# MB_Conn.net
KiCad netlist of a schematic drawn in Altium Designer
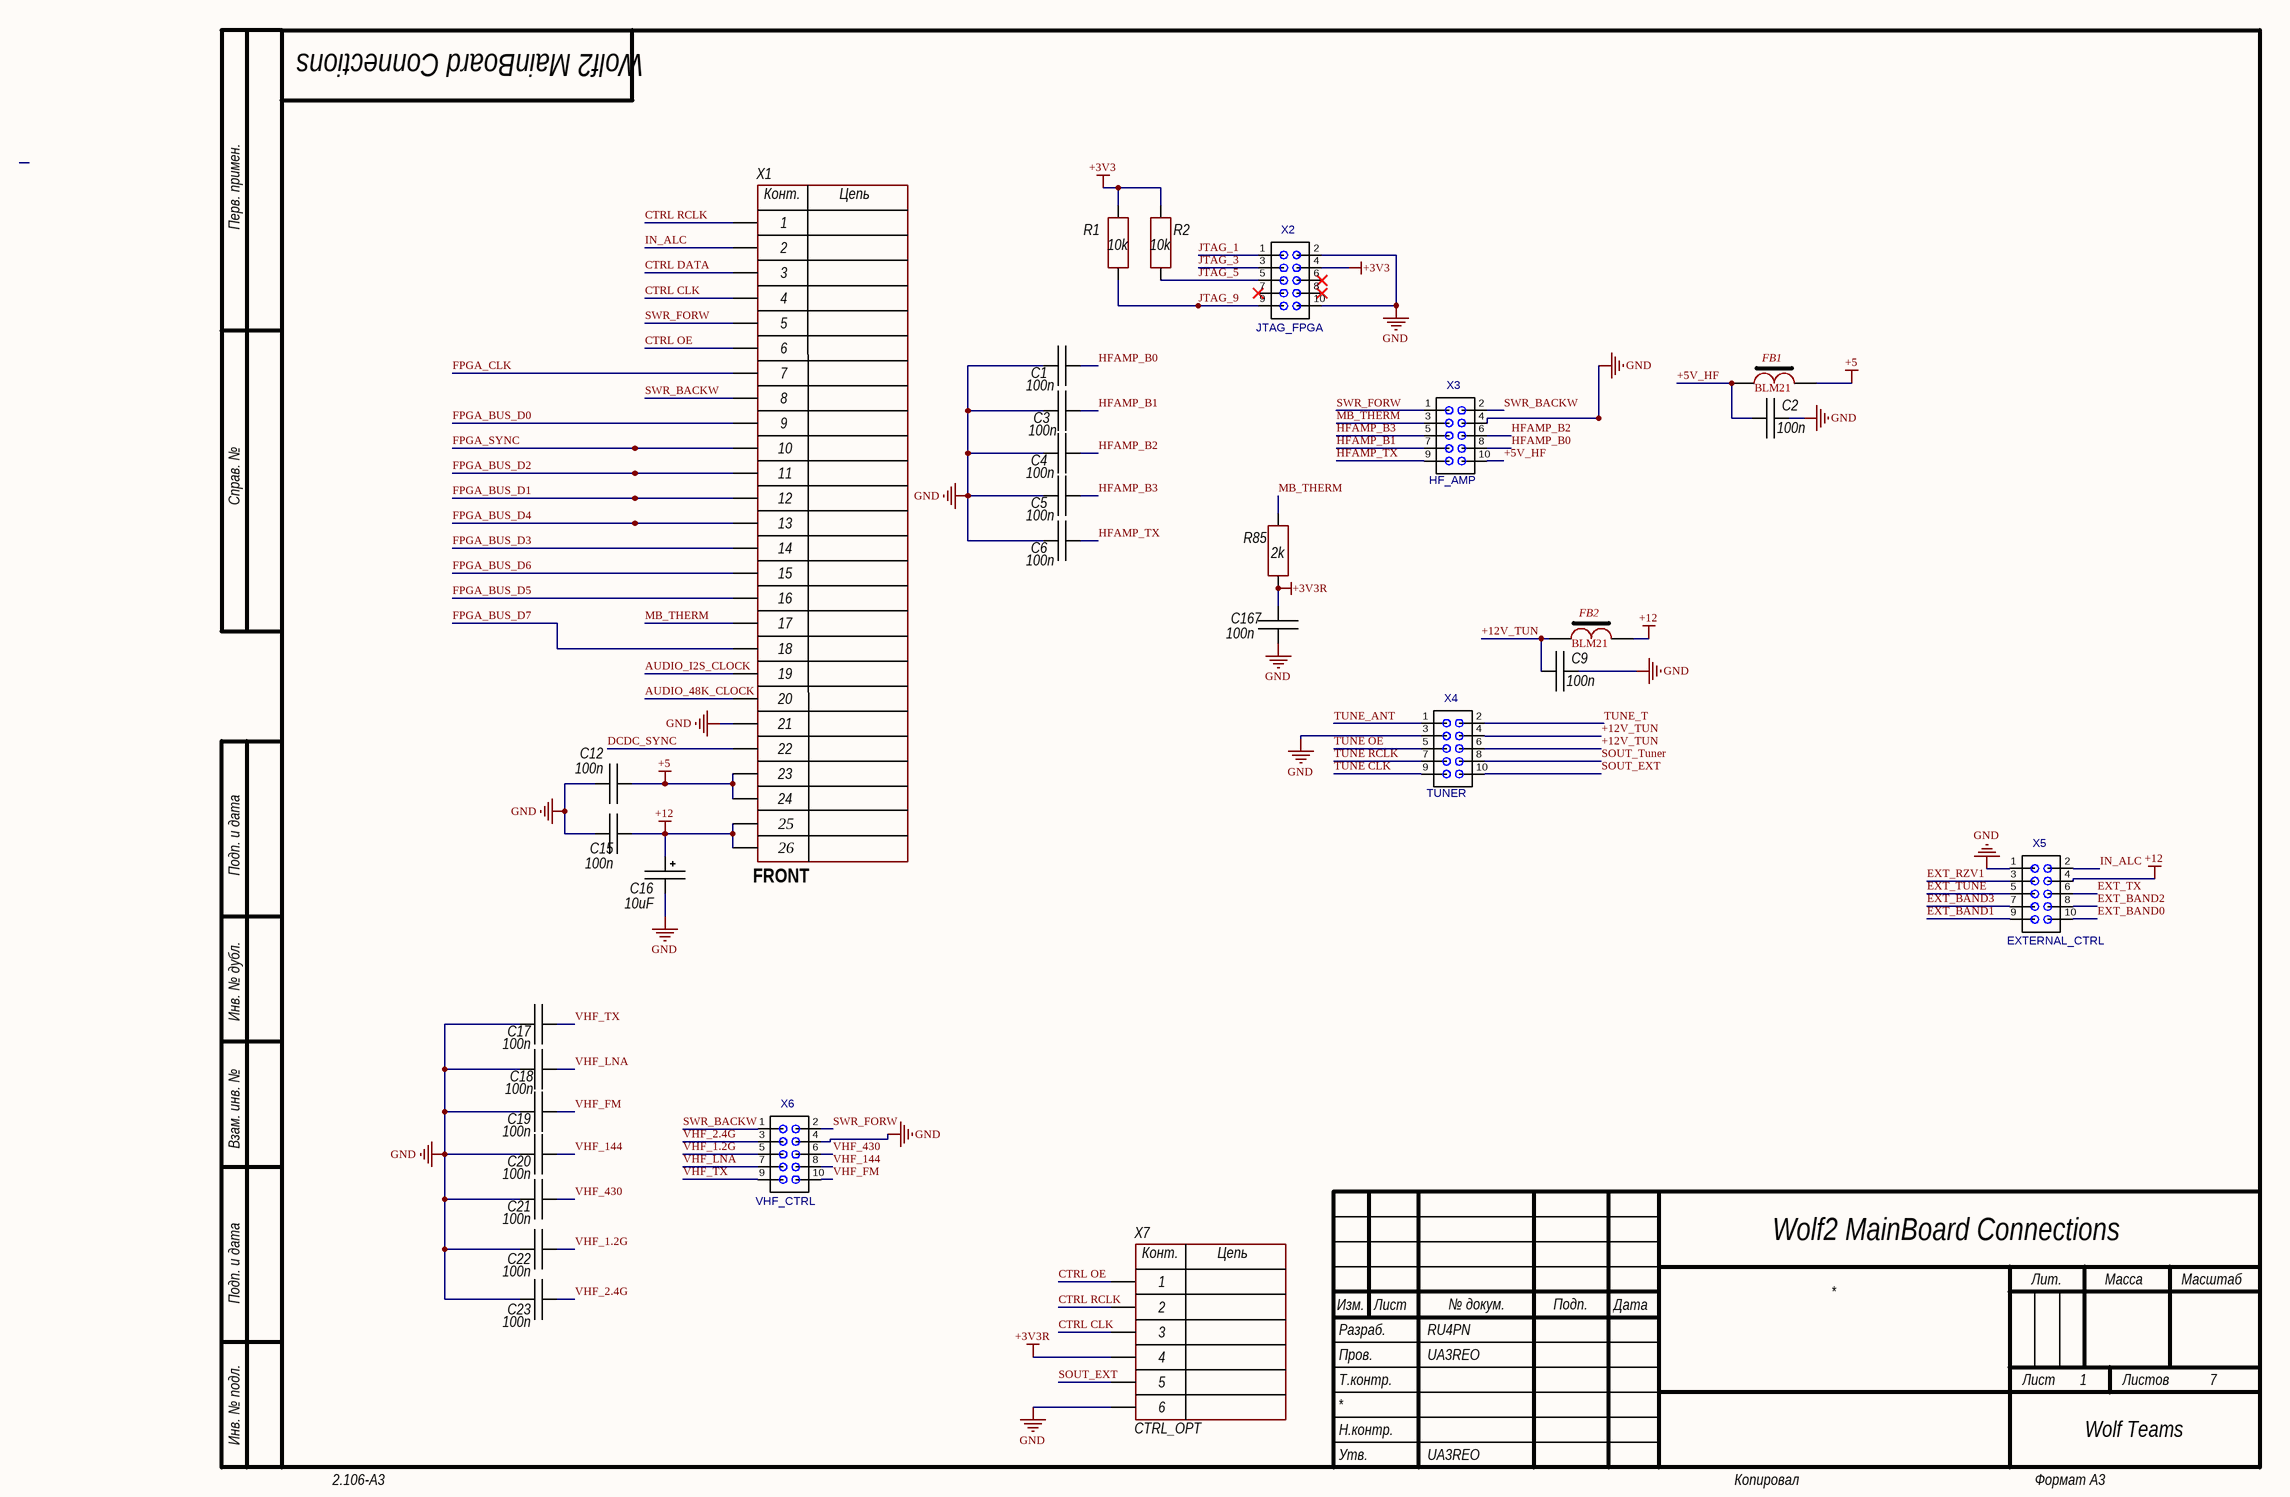
[diagram p0: MB_Conn.SchDoc]

(export (version "E")
  (design (tool "Eeschema 10.0.6"))
  (components
    (comp (ref "C1")
      (value "100n")
      (footprint "standard:CH0805C")
      (libsource (lib "Discrete") (part "Capacitor"))
    )
    (comp (ref "C2")
      (value "100n")
      (footprint "standard:CH0805C")
      (libsource (lib "Discrete") (part "Capacitor"))
    )
    (comp (ref "C3")
      (value "100n")
      (footprint "standard:CH0805C")
      (libsource (lib "Discrete") (part "Capacitor"))
    )
    (comp (ref "C4")
      (value "100n")
      (footprint "standard:CH0805C")
      (libsource (lib "Discrete") (part "Capacitor"))
    )
    (comp (ref "C5")
      (value "100n")
      (footprint "standard:CH0805C")
      (libsource (lib "Discrete") (part "Capacitor"))
    )
    (comp (ref "C6")
      (value "100n")
      (footprint "standard:CH0805C")
      (libsource (lib "Discrete") (part "Capacitor"))
    )
    (comp (ref "C9")
      (value "100n")
      (footprint "standard:CH0805C")
      (libsource (lib "Discrete") (part "Capacitor"))
    )
    (comp (ref "C12")
      (value "100n")
      (footprint "standard:CH0805C")
      (libsource (lib "Discrete") (part "Capacitor"))
    )
    (comp (ref "C15")
      (value "100n")
      (footprint "standard:CH0805C")
      (libsource (lib "Discrete") (part "Capacitor"))
    )
    (comp (ref "C16")
      (value "10uF")
      (footprint "standard:TANTAL_B")
      (libsource (lib "Discrete") (part "TantalCap"))
    )
    (comp (ref "C17")
      (value "100n")
      (footprint "standard:CH0805C")
      (libsource (lib "Discrete") (part "Capacitor"))
    )
    (comp (ref "C18")
      (value "100n")
      (footprint "standard:CH0805C")
      (libsource (lib "Discrete") (part "Capacitor"))
    )
    (comp (ref "C19")
      (value "100n")
      (footprint "standard:CH0805C")
      (libsource (lib "Discrete") (part "Capacitor"))
    )
    (comp (ref "C20")
      (value "100n")
      (footprint "standard:CH0805C")
      (libsource (lib "Discrete") (part "Capacitor"))
    )
    (comp (ref "C21")
      (value "100n")
      (footprint "standard:CH0805C")
      (libsource (lib "Discrete") (part "Capacitor"))
    )
    (comp (ref "C22")
      (value "100n")
      (footprint "standard:CH0805C")
      (libsource (lib "Discrete") (part "Capacitor"))
    )
    (comp (ref "C23")
      (value "100n")
      (footprint "standard:CH0805C")
      (libsource (lib "Discrete") (part "Capacitor"))
    )
    (comp (ref "C167")
      (value "100n")
      (footprint "standard:CH0805C")
      (libsource (lib "Discrete") (part "Capacitor"))
    )
    (comp (ref "FB1") (value "BLM21") (footprint "CH0805L") (libsource (lib "Discrete") (part "FB-1")))
    (comp (ref "FB2") (value "BLM21") (footprint "CH0805L") (libsource (lib "Discrete") (part "FB-1")))
    (comp (ref "R1")
      (value "10k")
      (footprint "standard:CH0805R")
      (libsource (lib "Discrete") (part "Resistor"))
    )
    (comp (ref "R2")
      (value "10k")
      (footprint "standard:CH0805R")
      (libsource (lib "Discrete") (part "Resistor"))
    )
    (comp (ref "R85") (value "2k") (footprint "standard:CH0805R") (libsource (lib "") (part "Resistor_1")))
    (comp (ref "X1")
      (value "FRONT")
      (footprint "CON: IDC-26")
      (libsource (lib "Connectors") (part "26-Connector"))
    )
    (comp (ref "X2")
      (value "JTAG_FPGA")
      (footprint "CON: BH-10")
      (description "2*5 Pin")
      (libsource (lib "*") (part "IDC10"))
    )
    (comp (ref "X3")
      (value "HF_AMP")
      (footprint "CON: BH-10")
      (description "2*5 Pin")
      (libsource (lib "*") (part "IDC10"))
    )
    (comp (ref "X4")
      (value "TUNER")
      (footprint "CON: BH-10")
      (description "2*5 Pin")
      (libsource (lib "*") (part "IDC10"))
    )
    (comp (ref "X5")
      (value "EXTERNAL_CTRL")
      (footprint "CON: BH-10")
      (description "2*5 Pin")
      (libsource (lib "*") (part "IDC10"))
    )
    (comp (ref "X6")
      (value "VHF_CTRL")
      (footprint "CON: BH-10")
      (description "2*5 Pin")
      (libsource (lib "*") (part "IDC10"))
    )
    (comp (ref "X7")
      (value "CTRL_OPT")
      (footprint "custom:CON: PBS-6")
      (libsource (lib "Connectors") (part "6-Connector"))
    )
  )
  (nets
    (net (code "1") (name "+3V3") (class "Default")
      (node (ref "R1") (pin "2") (pinfunction "2_2") (pintype "passive"))
      (node (ref "R2") (pin "2") (pinfunction "2_2") (pintype "passive"))
      (node (ref "X2") (pin "4") (pinfunction "4_4") (pintype "passive"))
    )
    (net (code "2") (name "+3V3R") (class "Default")
      (node (ref "C167") (pin "2") (pinfunction "2_2") (pintype "power_in"))
      (node (ref "R85") (pin "1") (pinfunction "1_1") (pintype "passive"))
      (node (ref "X7") (pin "4") (pinfunction "4_4") (pintype "power_in"))
    )
    (net (code "3") (name "+5") (class "Default")
      (node (ref "C12") (pin "1") (pinfunction "1_1") (pintype "power_in"))
      (node (ref "FB1") (pin "1") (pinfunction "1_1") (pintype "passive"))
      (node (ref "X1") (pin "23") (pinfunction "23_23") (pintype "power_in"))
      (node (ref "X1") (pin "24") (pinfunction "24_24") (pintype "power_in"))
    )
    (net (code "4") (name "+12") (class "Default")
      (node (ref "C15") (pin "1") (pinfunction "1_1") (pintype "power_in"))
      (node (ref "C16") (pin "1") (pinfunction "1_1") (pintype "power_in"))
      (node (ref "FB2") (pin "1") (pinfunction "1_1") (pintype "passive"))
      (node (ref "X1") (pin "25") (pinfunction "25_25") (pintype "power_in"))
      (node (ref "X1") (pin "26") (pinfunction "26_26") (pintype "passive"))
      (node (ref "X5") (pin "4") (pinfunction "4_4") (pintype "passive"))
    )
    (net (code "5") (name "/+5V_HF") (class "Default")
      (node (ref "C2") (pin "1") (pinfunction "1_1") (pintype "power_in"))
      (node (ref "FB1") (pin "2") (pinfunction "2_2") (pintype "passive"))
      (node (ref "X3") (pin "10") (pinfunction "10_10") (pintype "passive"))
    )
    (net (code "6") (name "/+12V_TUN") (class "Default")
      (node (ref "C9") (pin "1") (pinfunction "1_1") (pintype "power_in"))
      (node (ref "FB2") (pin "2") (pinfunction "2_2") (pintype "passive"))
      (node (ref "X4") (pin "4") (pinfunction "4_4") (pintype "passive"))
      (node (ref "X4") (pin "6") (pinfunction "6_6") (pintype "passive"))
    )
    (net (code "7") (name "/AUDIO_48K_CLOCK") (class "Default")
      (node (ref "X1") (pin "20") (pinfunction "20_20") (pintype "power_in"))
    )
    (net (code "8") (name "/AUDIO_I2S_CLOCK") (class "Default")
      (node (ref "X1") (pin "19") (pinfunction "19_19") (pintype "power_in"))
    )
    (net (code "9") (name "/CTRL CLK") (class "Default")
      (node (ref "X1") (pin "4") (pinfunction "4_4") (pintype "power_in"))
      (node (ref "X7") (pin "3") (pinfunction "3_3") (pintype "power_in"))
    )
    (net (code "10") (name "/CTRL DATA") (class "Default")
      (node (ref "X1") (pin "3") (pinfunction "3_3") (pintype "power_in"))
    )
    (net (code "11") (name "/CTRL OE") (class "Default")
      (node (ref "X1") (pin "6") (pinfunction "6_6") (pintype "power_in"))
      (node (ref "X7") (pin "1") (pinfunction "1_1") (pintype "passive"))
    )
    (net (code "12") (name "/CTRL RCLK") (class "Default")
      (node (ref "X1") (pin "1") (pinfunction "1_1") (pintype "passive"))
      (node (ref "X7") (pin "2") (pinfunction "2_2") (pintype "passive"))
    )
    (net (code "13") (name "/DCDC_SYNC") (class "Default")
      (node (ref "X1") (pin "22") (pinfunction "22_22") (pintype "power_in"))
    )
    (net (code "14") (name "/EXT_BAND0") (class "Default")
      (node (ref "X5") (pin "10") (pinfunction "10_10") (pintype "passive"))
    )
    (net (code "15") (name "/EXT_BAND1") (class "Default")
      (node (ref "X5") (pin "9") (pinfunction "9_9") (pintype "passive"))
    )
    (net (code "16") (name "/EXT_BAND2") (class "Default")
      (node (ref "X5") (pin "8") (pinfunction "8_8") (pintype "passive"))
    )
    (net (code "17") (name "/EXT_BAND3") (class "Default")
      (node (ref "X5") (pin "7") (pinfunction "7_7") (pintype "passive"))
    )
    (net (code "18") (name "/EXT_RZV1") (class "Default")
      (node (ref "X5") (pin "3") (pinfunction "3_3") (pintype "passive"))
    )
    (net (code "19") (name "/EXT_TUNE") (class "Default")
      (node (ref "X5") (pin "5") (pinfunction "5_5") (pintype "passive"))
    )
    (net (code "20") (name "/EXT_TX") (class "Default")
      (node (ref "X5") (pin "6") (pinfunction "6_6") (pintype "passive"))
    )
    (net (code "21") (name "/FPGA_BUS_D0") (class "Default")
      (node (ref "X1") (pin "9") (pinfunction "9_9") (pintype "power_in"))
    )
    (net (code "22") (name "/FPGA_BUS_D1") (class "Default")
      (node (ref "X1") (pin "12") (pinfunction "12_12") (pintype "power_in"))
    )
    (net (code "23") (name "/FPGA_BUS_D2") (class "Default")
      (node (ref "X1") (pin "11") (pinfunction "11_11") (pintype "power_in"))
    )
    (net (code "24") (name "/FPGA_BUS_D3") (class "Default")
      (node (ref "X1") (pin "14") (pinfunction "14_14") (pintype "power_in"))
    )
    (net (code "25") (name "/FPGA_BUS_D4") (class "Default")
      (node (ref "X1") (pin "13") (pinfunction "13_13") (pintype "power_in"))
    )
    (net (code "26") (name "/FPGA_BUS_D5") (class "Default")
      (node (ref "X1") (pin "16") (pinfunction "16_16") (pintype "power_in"))
    )
    (net (code "27") (name "/FPGA_BUS_D6") (class "Default")
      (node (ref "X1") (pin "15") (pinfunction "15_15") (pintype "power_in"))
    )
    (net (code "28") (name "/FPGA_BUS_D7") (class "Default")
      (node (ref "X1") (pin "18") (pinfunction "18_18") (pintype "power_in"))
    )
    (net (code "29") (name "/FPGA_CLK") (class "Default")
      (node (ref "X1") (pin "7") (pinfunction "7_7") (pintype "power_in"))
    )
    (net (code "30") (name "/FPGA_SYNC") (class "Default")
      (node (ref "X1") (pin "10") (pinfunction "10_10") (pintype "power_in"))
    )
    (net (code "31") (name "/HFAMP_B0") (class "Default")
      (node (ref "C1") (pin "1") (pinfunction "1_1") (pintype "power_in"))
      (node (ref "X3") (pin "8") (pinfunction "8_8") (pintype "passive"))
    )
    (net (code "32") (name "/HFAMP_B1") (class "Default")
      (node (ref "C3") (pin "1") (pinfunction "1_1") (pintype "power_in"))
      (node (ref "X3") (pin "7") (pinfunction "7_7") (pintype "passive"))
    )
    (net (code "33") (name "/HFAMP_B2") (class "Default")
      (node (ref "C4") (pin "1") (pinfunction "1_1") (pintype "power_in"))
      (node (ref "X3") (pin "6") (pinfunction "6_6") (pintype "passive"))
    )
    (net (code "34") (name "/HFAMP_B3") (class "Default")
      (node (ref "C5") (pin "1") (pinfunction "1_1") (pintype "power_in"))
      (node (ref "X3") (pin "5") (pinfunction "5_5") (pintype "passive"))
    )
    (net (code "35") (name "/HFAMP_TX") (class "Default")
      (node (ref "C6") (pin "1") (pinfunction "1_1") (pintype "power_in"))
      (node (ref "X3") (pin "9") (pinfunction "9_9") (pintype "passive"))
    )
    (net (code "36") (name "/IN_ALC") (class "Default")
      (node (ref "X1") (pin "2") (pinfunction "2_2") (pintype "passive"))
      (node (ref "X5") (pin "2") (pinfunction "2_2") (pintype "passive"))
    )
    (net (code "37") (name "/JTAG_1") (class "Default")
      (node (ref "X2") (pin "1") (pinfunction "1_1") (pintype "passive"))
    )
    (net (code "38") (name "/JTAG_3") (class "Default")
      (node (ref "X2") (pin "3") (pinfunction "3_3") (pintype "passive"))
    )
    (net (code "39") (name "/JTAG_5") (class "Default")
      (node (ref "R2") (pin "1") (pinfunction "1_1") (pintype "passive"))
      (node (ref "X2") (pin "5") (pinfunction "5_5") (pintype "passive"))
    )
    (net (code "40") (name "/JTAG_9") (class "Default")
      (node (ref "R1") (pin "1") (pinfunction "1_1") (pintype "passive"))
      (node (ref "X2") (pin "9") (pinfunction "9_9") (pintype "passive"))
    )
    (net (code "41") (name "/MB_THERM") (class "Default")
      (node (ref "R85") (pin "2") (pinfunction "2_2") (pintype "passive"))
      (node (ref "X1") (pin "17") (pinfunction "17_17") (pintype "power_in"))
      (node (ref "X3") (pin "3") (pinfunction "3_3") (pintype "passive"))
    )
    (net (code "42") (name "/SOUT_EXT") (class "Default")
      (node (ref "X4") (pin "10") (pinfunction "10_10") (pintype "passive"))
      (node (ref "X7") (pin "5") (pinfunction "5_5") (pintype "power_in"))
    )
    (net (code "43") (name "/SOUT_Tuner") (class "Default")
      (node (ref "X4") (pin "8") (pinfunction "8_8") (pintype "passive"))
    )
    (net (code "44") (name "/SWR_BACKW") (class "Default")
      (node (ref "X1") (pin "8") (pinfunction "8_8") (pintype "power_in"))
      (node (ref "X3") (pin "2") (pinfunction "2_2") (pintype "passive"))
      (node (ref "X6") (pin "1") (pinfunction "1_1") (pintype "passive"))
    )
    (net (code "45") (name "/SWR_FORW") (class "Default")
      (node (ref "X1") (pin "5") (pinfunction "5_5") (pintype "power_in"))
      (node (ref "X3") (pin "1") (pinfunction "1_1") (pintype "passive"))
      (node (ref "X6") (pin "2") (pinfunction "2_2") (pintype "passive"))
    )
    (net (code "46") (name "/TUNE CLK") (class "Default")
      (node (ref "X4") (pin "9") (pinfunction "9_9") (pintype "passive"))
    )
    (net (code "47") (name "/TUNE OE") (class "Default")
      (node (ref "X4") (pin "5") (pinfunction "5_5") (pintype "passive"))
    )
    (net (code "48") (name "/TUNE RCLK") (class "Default")
      (node (ref "X4") (pin "7") (pinfunction "7_7") (pintype "passive"))
    )
    (net (code "49") (name "/TUNE_ANT") (class "Default")
      (node (ref "X4") (pin "1") (pinfunction "1_1") (pintype "passive"))
    )
    (net (code "50") (name "/TUNE_T") (class "Default")
      (node (ref "X4") (pin "2") (pinfunction "2_2") (pintype "passive"))
    )
    (net (code "51") (name "/VHF_1.2G") (class "Default")
      (node (ref "C22") (pin "1") (pinfunction "1_1") (pintype "power_in"))
      (node (ref "X6") (pin "5") (pinfunction "5_5") (pintype "passive"))
    )
    (net (code "52") (name "/VHF_2.4G") (class "Default")
      (node (ref "C23") (pin "1") (pinfunction "1_1") (pintype "power_in"))
      (node (ref "X6") (pin "3") (pinfunction "3_3") (pintype "passive"))
    )
    (net (code "53") (name "/VHF_144") (class "Default")
      (node (ref "C20") (pin "1") (pinfunction "1_1") (pintype "power_in"))
      (node (ref "X6") (pin "8") (pinfunction "8_8") (pintype "passive"))
    )
    (net (code "54") (name "/VHF_430") (class "Default")
      (node (ref "C21") (pin "1") (pinfunction "1_1") (pintype "power_in"))
      (node (ref "X6") (pin "6") (pinfunction "6_6") (pintype "passive"))
    )
    (net (code "55") (name "/VHF_FM") (class "Default")
      (node (ref "C19") (pin "1") (pinfunction "1_1") (pintype "power_in"))
      (node (ref "X6") (pin "10") (pinfunction "10_10") (pintype "passive"))
    )
    (net (code "56") (name "/VHF_LNA") (class "Default")
      (node (ref "C18") (pin "1") (pinfunction "1_1") (pintype "power_in"))
      (node (ref "X6") (pin "7") (pinfunction "7_7") (pintype "passive"))
    )
    (net (code "57") (name "/VHF_TX") (class "Default")
      (node (ref "C17") (pin "1") (pinfunction "1_1") (pintype "power_in"))
      (node (ref "X6") (pin "9") (pinfunction "9_9") (pintype "passive"))
    )
    (net (code "58") (name "GND") (class "Default")
      (node (ref "C1") (pin "2") (pinfunction "2_2") (pintype "power_in"))
      (node (ref "C12") (pin "2") (pinfunction "2_2") (pintype "power_in"))
      (node (ref "C15") (pin "2") (pinfunction "2_2") (pintype "power_in"))
      (node (ref "C16") (pin "2") (pinfunction "2_2") (pintype "power_in"))
      (node (ref "C167") (pin "1") (pinfunction "1_1") (pintype "power_in"))
      (node (ref "C17") (pin "2") (pinfunction "2_2") (pintype "power_in"))
      (node (ref "C18") (pin "2") (pinfunction "2_2") (pintype "power_in"))
      (node (ref "C19") (pin "2") (pinfunction "2_2") (pintype "power_in"))
      (node (ref "C2") (pin "2") (pinfunction "2_2") (pintype "power_in"))
      (node (ref "C20") (pin "2") (pinfunction "2_2") (pintype "power_in"))
      (node (ref "C21") (pin "2") (pinfunction "2_2") (pintype "power_in"))
      (node (ref "C22") (pin "2") (pinfunction "2_2") (pintype "power_in"))
      (node (ref "C23") (pin "2") (pinfunction "2_2") (pintype "power_in"))
      (node (ref "C3") (pin "2") (pinfunction "2_2") (pintype "power_in"))
      (node (ref "C4") (pin "2") (pinfunction "2_2") (pintype "power_in"))
      (node (ref "C5") (pin "2") (pinfunction "2_2") (pintype "power_in"))
      (node (ref "C6") (pin "2") (pinfunction "2_2") (pintype "power_in"))
      (node (ref "C9") (pin "2") (pinfunction "2_2") (pintype "power_in"))
      (node (ref "X1") (pin "21") (pinfunction "21_21") (pintype "power_in"))
      (node (ref "X2") (pin "10") (pinfunction "10_10") (pintype "passive"))
      (node (ref "X2") (pin "2") (pinfunction "2_2") (pintype "passive"))
      (node (ref "X3") (pin "4") (pinfunction "4_4") (pintype "passive"))
      (node (ref "X4") (pin "3") (pinfunction "3_3") (pintype "passive"))
      (node (ref "X5") (pin "1") (pinfunction "1_1") (pintype "passive"))
      (node (ref "X6") (pin "4") (pinfunction "4_4") (pintype "passive"))
      (node (ref "X7") (pin "6") (pinfunction "6_6") (pintype "power_in"))
    )
    (net (code "59") (name "unconnected-(X2-Pad6)") (class "Default")
      (node (ref "X2") (pin "6") (pinfunction "6_6") (pintype "passive+no_connect"))
    )
    (net (code "60") (name "unconnected-(X2-Pad7)") (class "Default")
      (node (ref "X2") (pin "7") (pinfunction "7_7") (pintype "passive+no_connect"))
    )
    (net (code "61") (name "unconnected-(X2-Pad8)") (class "Default")
      (node (ref "X2") (pin "8") (pinfunction "8_8") (pintype "passive+no_connect"))
    )
  )
)
